# TPS5430.net
KiCad netlist of a schematic drawn in Altium Designer
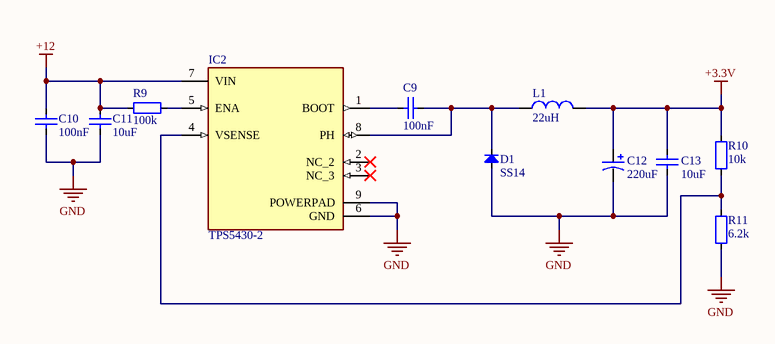
[diagram p0: TPS5430.SchDoc]

(export (version "E")
  (design (tool "Eeschema 10.0.6"))
  (components
    (comp (ref "C9")
      (value "100nF")
      (footprint "CAP_0805")
      (description "Capacitor")
      (fields (field (name "PUBLISHER") "Altium Limited"))
      (libsource (lib "My Library") (part "CapSMD"))
    )
    (comp (ref "C10")
      (value "100nF")
      (footprint "CAP_0805")
      (description "Capacitor")
      (fields (field (name "PUBLISHER") "Altium Limited"))
      (libsource (lib "My Library") (part "CapSMD"))
    )
    (comp (ref "C11")
      (value "10uF")
      (footprint "CAP_0805")
      (description "Capacitor")
      (fields (field (name "PUBLISHER") "Altium Limited"))
      (libsource (lib "My Library") (part "CapSMD"))
    )
    (comp (ref "C12")
      (value "220uF")
      (footprint "CAP_7343")
      (description "Polazied Tantalum Capacitor")
      (libsource (lib "My Library") (part "CAP_TAN_SMD"))
    )
    (comp (ref "C13")
      (value "10uF")
      (footprint "CAP_0805")
      (description "Capacitor")
      (fields (field (name "PUBLISHER") "Altium Limited"))
      (libsource (lib "My Library") (part "CapSMD"))
    )
    (comp (ref "D1")
      (value "SS14")
      (footprint "DO-214AC(SMA)")
      (description "SS34 Diode Schottky 3A 40V SMA(DO-214AC)")
      (fields (field (name "PUBLISHER") "Altium Limited"))
      (libsource (lib "My Library") (part "Diode SMD"))
    )
    (comp (ref "IC2")
      (value "TPS5430-2")
      (footprint "TPS5430")
      (libsource (lib "My Library") (part "TPS5430-2"))
    )
    (comp (ref "L1")
      (value "22uH")
      (footprint "L_SMD")
      (description "CD73R 22uH 1.23A 7345")
      (libsource (lib "My Library") (part "Inductor"))
    )
    (comp (ref "R9")
      (value "100k")
      (footprint "RES-SMD-0805")
      (description "Resistor")
      (fields
        (field (name "MANUFACTURER") "Generic Components")
        (field (name "PUBLISHER") "Altium Hobart Technology Centre")
      )
      (libsource (lib "My Library") (part "Resistor - SMD"))
    )
    (comp (ref "R10")
      (value "10k")
      (footprint "RES-SMD-0805")
      (description "Resistor")
      (fields
        (field (name "MANUFACTURER") "Generic Components")
        (field (name "PUBLISHER") "Altium Hobart Technology Centre")
      )
      (libsource (lib "My Library") (part "Resistor - SMD"))
    )
    (comp (ref "R11")
      (value "6.2k")
      (footprint "RES-SMD-0805")
      (description "Resistor")
      (fields
        (field (name "MANUFACTURER") "Generic Components")
        (field (name "PUBLISHER") "Altium Hobart Technology Centre")
      )
      (libsource (lib "My Library") (part "Resistor - SMD"))
    )
  )
  (nets
    (net (code "1") (name "+3.3V") (class "Default")
      (node (ref "C12") (pin "1") (pinfunction "1_1") (pintype "passive"))
      (node (ref "C13") (pin "1") (pinfunction "1_1") (pintype "passive"))
      (node (ref "L1") (pin "2") (pinfunction "2_2") (pintype "passive"))
      (node (ref "R10") (pin "2") (pinfunction "2_2") (pintype "passive"))
    )
    (net (code "2") (name "+12") (class "Default")
      (node (ref "C10") (pin "2") (pinfunction "2_2") (pintype "passive"))
      (node (ref "C11") (pin "2") (pinfunction "2_2") (pintype "passive"))
      (node (ref "IC2") (pin "7") (pinfunction "VIN_7") (pintype "power_in"))
      (node (ref "R9") (pin "1") (pinfunction "1_1") (pintype "passive"))
    )
    (net (code "3") (name "GND") (class "Default")
      (node (ref "C10") (pin "1") (pinfunction "1_1") (pintype "passive"))
      (node (ref "C11") (pin "1") (pinfunction "1_1") (pintype "passive"))
      (node (ref "C12") (pin "2") (pinfunction "2_2") (pintype "passive"))
      (node (ref "C13") (pin "2") (pinfunction "2_2") (pintype "passive"))
      (node (ref "D1") (pin "1") (pinfunction "A_1") (pintype "passive"))
      (node (ref "IC2") (pin "6") (pinfunction "GND_6") (pintype "power_in"))
      (node (ref "IC2") (pin "9") (pinfunction "POWERPAD_9") (pintype "power_in"))
      (node (ref "R11") (pin "1") (pinfunction "1_1") (pintype "passive"))
    )
    (net (code "4") (name "Net-(D1-K)") (class "Default")
      (node (ref "C9") (pin "1") (pinfunction "1_1") (pintype "passive"))
      (node (ref "D1") (pin "2") (pinfunction "K_2") (pintype "passive"))
      (node (ref "IC2") (pin "8") (pinfunction "PH_8") (pintype "bidirectional"))
      (node (ref "L1") (pin "1") (pinfunction "1_1") (pintype "passive"))
    )
    (net (code "5") (name "Net-(IC2-BOOT)") (class "Default")
      (node (ref "C9") (pin "2") (pinfunction "2_2") (pintype "passive"))
      (node (ref "IC2") (pin "1") (pinfunction "BOOT_1") (pintype "output"))
    )
    (net (code "6") (name "Net-(IC2-ENA)") (class "Default")
      (node (ref "IC2") (pin "5") (pinfunction "ENA_5") (pintype "input"))
      (node (ref "R9") (pin "2") (pinfunction "2_2") (pintype "passive"))
    )
    (net (code "7") (name "Net-(IC2-VSENSE)") (class "Default")
      (node (ref "IC2") (pin "4") (pinfunction "VSENSE_4") (pintype "input"))
      (node (ref "R10") (pin "1") (pinfunction "1_1") (pintype "passive"))
      (node (ref "R11") (pin "2") (pinfunction "2_2") (pintype "passive"))
    )
    (net (code "8") (name "unconnected-(IC2-NC_2-Pad2)") (class "Default")
      (node (ref "IC2") (pin "2") (pinfunction "NC_2_2") (pintype "input+no_connect"))
    )
    (net (code "9") (name "unconnected-(IC2-NC_3-Pad3)") (class "Default")
      (node (ref "IC2") (pin "3") (pinfunction "NC_3_3") (pintype "input+no_connect"))
    )
  )
)
